# SCH_Potensiometers_2024-04-15.net
KiCad netlist of a schematic drawn in EasyEDA
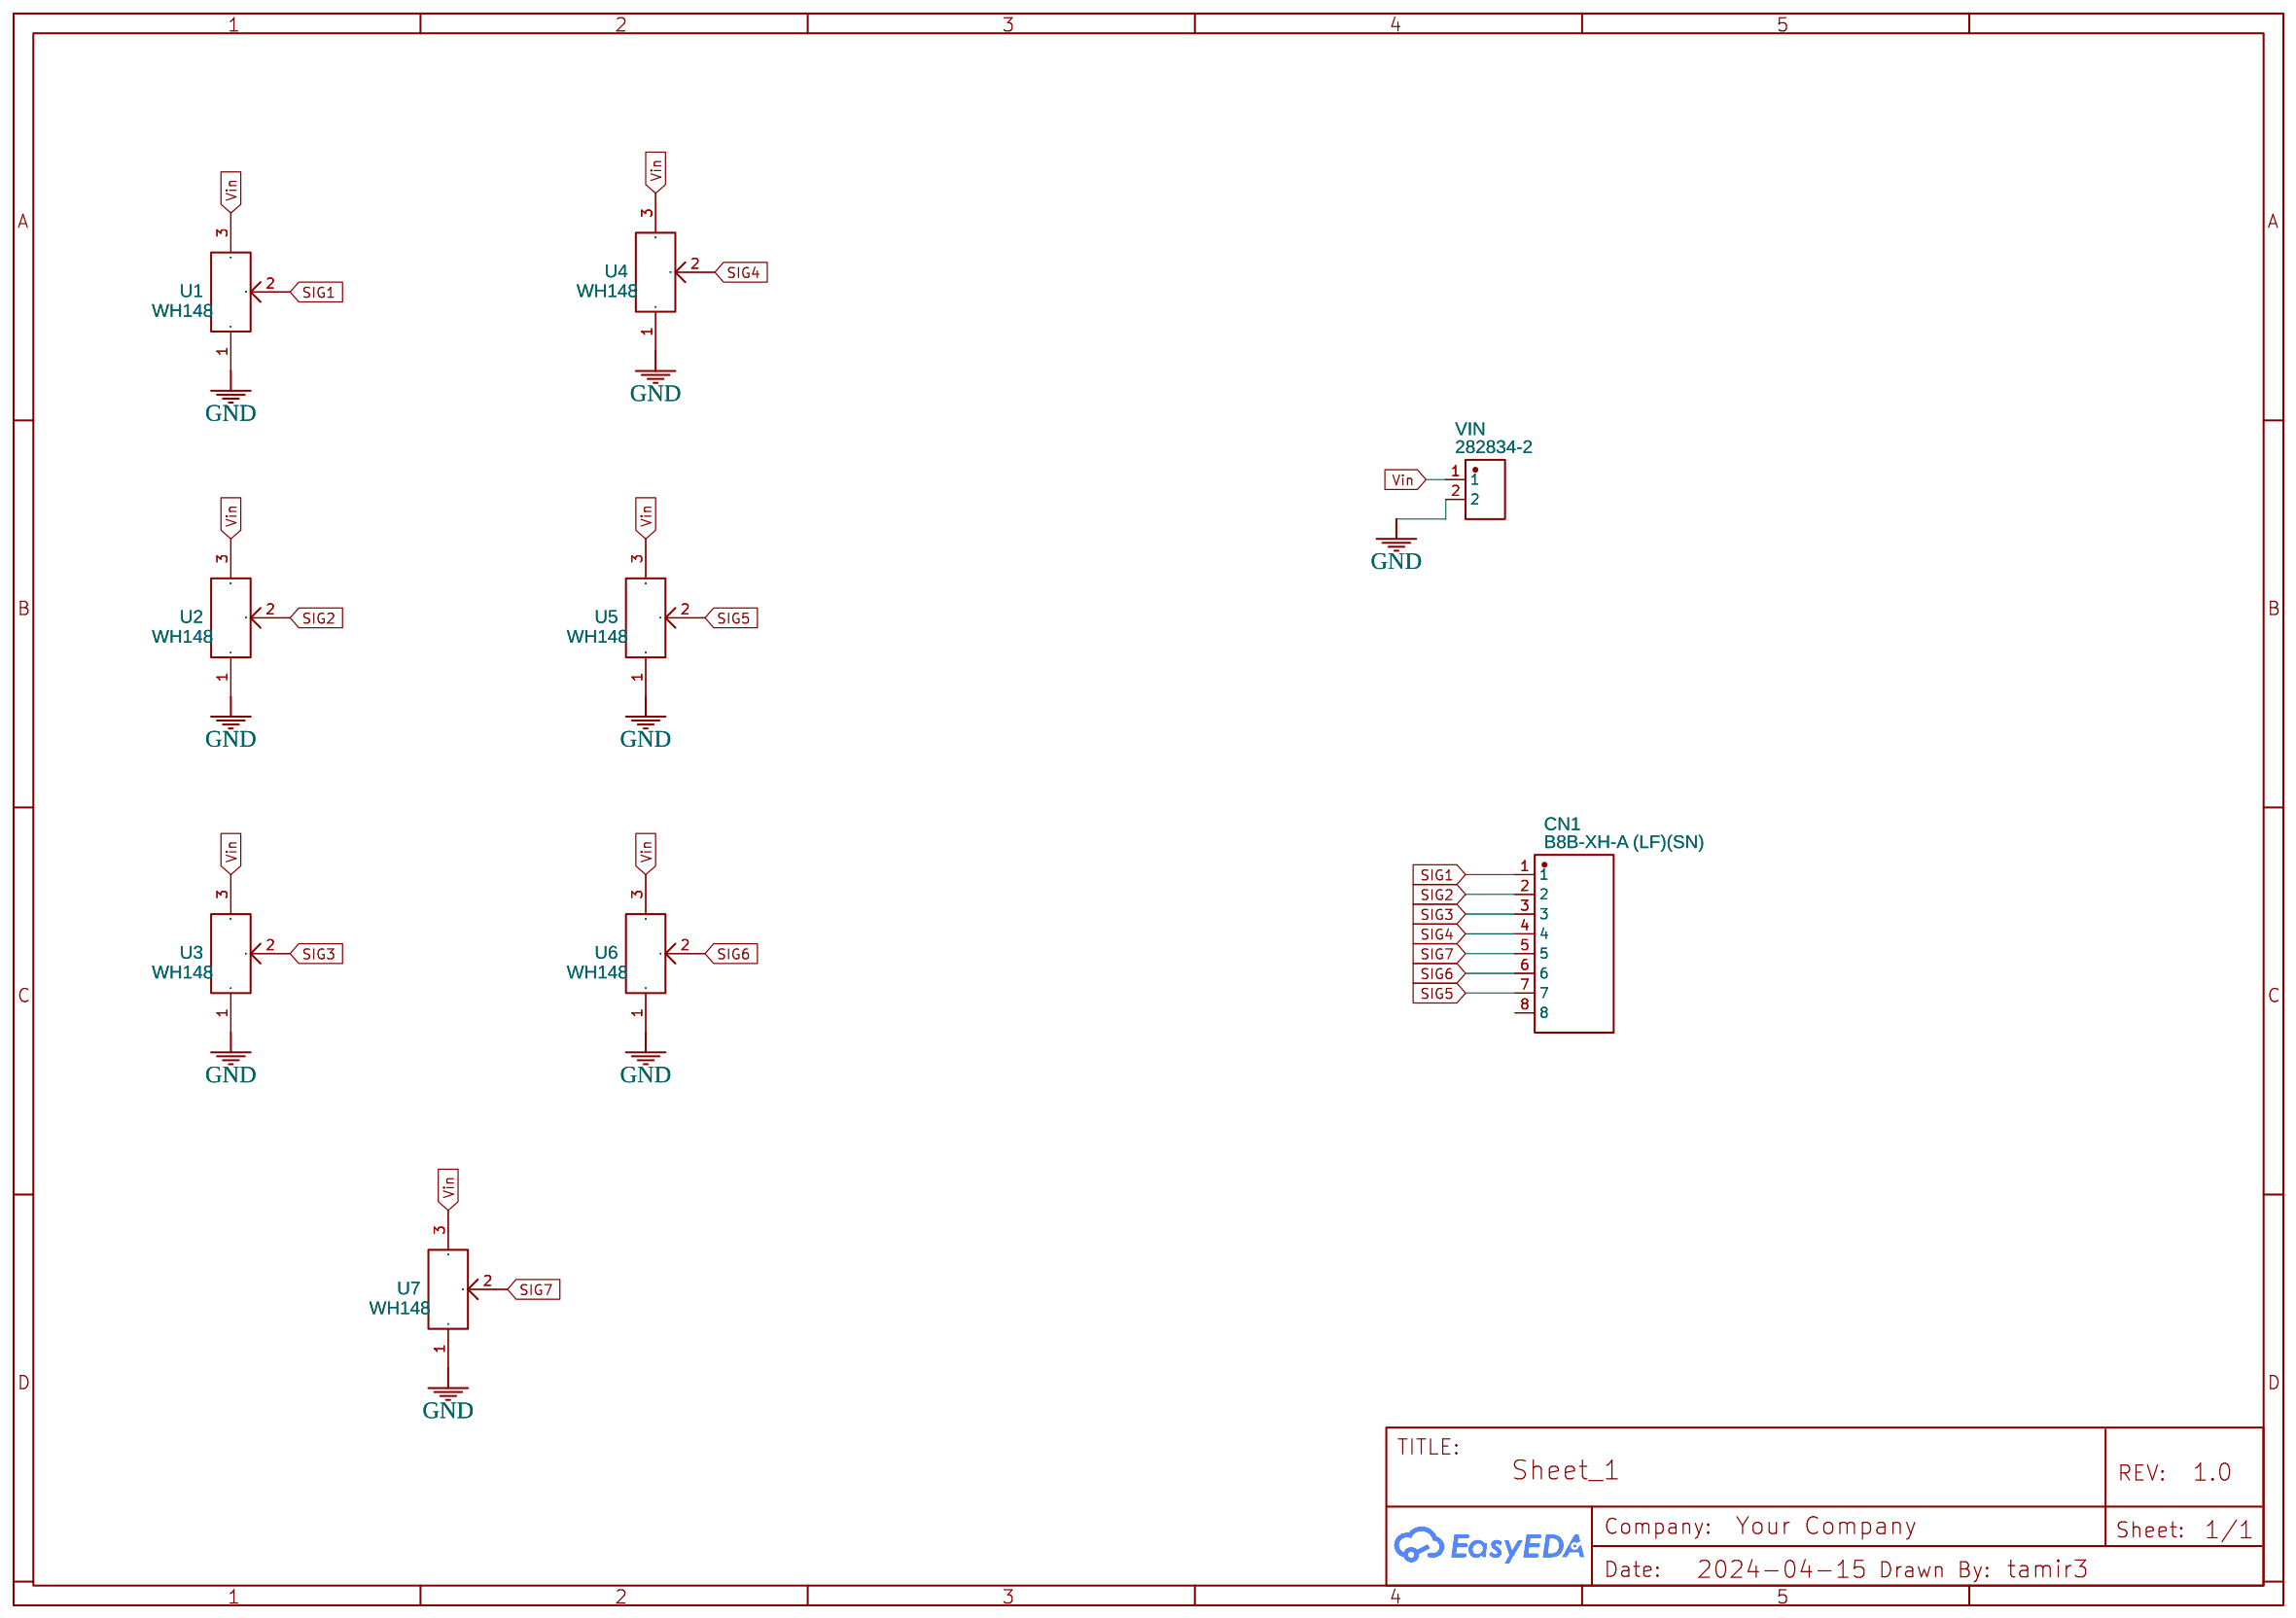
[diagram p0: schematic sheet]

(export (version "E")
  (design (tool "Eeschema 10.0.6"))
  (components
    (comp (ref "CN1")
      (value "B8B-XH-A (LF)(SN)")
      (fields (field (name "Manufacturer Part") "B8B-XH-A(LF)(SN)") (field (name "Manufacturer") "JST"))
      (libsource (lib "") (part "B8B-XH-A (LF)(SN)"))
    )
    (comp (ref "U1") (value "WH148") (libsource (lib "") (part "WH148 POTENZIOMETRO A SALDARE ORIZZONTALE")))
    (comp (ref "U2") (value "WH148") (libsource (lib "") (part "WH148 POTENZIOMETRO A SALDARE ORIZZONTALE")))
    (comp (ref "U3") (value "WH148") (libsource (lib "") (part "WH148 POTENZIOMETRO A SALDARE ORIZZONTALE")))
    (comp (ref "U4") (value "WH148") (libsource (lib "") (part "WH148 POTENZIOMETRO A SALDARE ORIZZONTALE")))
    (comp (ref "U5") (value "WH148") (libsource (lib "") (part "WH148 POTENZIOMETRO A SALDARE ORIZZONTALE")))
    (comp (ref "U6") (value "WH148") (libsource (lib "") (part "WH148 POTENZIOMETRO A SALDARE ORIZZONTALE")))
    (comp (ref "U7") (value "WH148") (libsource (lib "") (part "WH148 POTENZIOMETRO A SALDARE ORIZZONTALE")))
    (comp (ref "VIN")
      (value "282834-2")
      (fields (field (name "Manufacturer") "TE Connectivity(泰科电子)"))
      (libsource (lib "") (part "282834-2"))
    )
  )
  (nets
    (net (code "1") (name "GND") (class "Default")
      (node (ref "U1") (pin "1") (pinfunction "T1_1") (pintype "unspecified"))
      (node (ref "U2") (pin "1") (pinfunction "T1_1") (pintype "unspecified"))
      (node (ref "U3") (pin "1") (pinfunction "T1_1") (pintype "unspecified"))
      (node (ref "U4") (pin "1") (pinfunction "T1_1") (pintype "unspecified"))
      (node (ref "U5") (pin "1") (pinfunction "T1_1") (pintype "unspecified"))
      (node (ref "U6") (pin "1") (pinfunction "T1_1") (pintype "unspecified"))
      (node (ref "U7") (pin "1") (pinfunction "T1_1") (pintype "unspecified"))
      (node (ref "VIN") (pin "2") (pinfunction "2_2") (pintype "unspecified"))
    )
    (net (code "2") (name "SIG1") (class "Default")
      (node (ref "CN1") (pin "1") (pinfunction "1_1") (pintype "unspecified"))
      (node (ref "U1") (pin "2") (pinfunction "T2_2") (pintype "unspecified"))
    )
    (net (code "3") (name "SIG2") (class "Default")
      (node (ref "CN1") (pin "2") (pinfunction "2_2") (pintype "unspecified"))
      (node (ref "U2") (pin "2") (pinfunction "T2_2") (pintype "unspecified"))
    )
    (net (code "4") (name "SIG3") (class "Default")
      (node (ref "CN1") (pin "3") (pinfunction "3_3") (pintype "unspecified"))
      (node (ref "U3") (pin "2") (pinfunction "T2_2") (pintype "unspecified"))
    )
    (net (code "5") (name "SIG4") (class "Default")
      (node (ref "CN1") (pin "4") (pinfunction "4_4") (pintype "unspecified"))
      (node (ref "U4") (pin "2") (pinfunction "T2_2") (pintype "unspecified"))
    )
    (net (code "6") (name "SIG5") (class "Default")
      (node (ref "CN1") (pin "7") (pinfunction "7_7") (pintype "unspecified"))
      (node (ref "U5") (pin "2") (pinfunction "T2_2") (pintype "unspecified"))
    )
    (net (code "7") (name "SIG6") (class "Default")
      (node (ref "CN1") (pin "6") (pinfunction "6_6") (pintype "unspecified"))
      (node (ref "U6") (pin "2") (pinfunction "T2_2") (pintype "unspecified"))
    )
    (net (code "8") (name "SIG7") (class "Default")
      (node (ref "CN1") (pin "5") (pinfunction "5_5") (pintype "unspecified"))
      (node (ref "U7") (pin "2") (pinfunction "T2_2") (pintype "unspecified"))
    )
    (net (code "9") (name "Vin") (class "Default")
      (node (ref "U1") (pin "3") (pinfunction "T3_3") (pintype "unspecified"))
      (node (ref "U2") (pin "3") (pinfunction "T3_3") (pintype "unspecified"))
      (node (ref "U3") (pin "3") (pinfunction "T3_3") (pintype "unspecified"))
      (node (ref "U4") (pin "3") (pinfunction "T3_3") (pintype "unspecified"))
      (node (ref "U5") (pin "3") (pinfunction "T3_3") (pintype "unspecified"))
      (node (ref "U6") (pin "3") (pinfunction "T3_3") (pintype "unspecified"))
      (node (ref "U7") (pin "3") (pinfunction "T3_3") (pintype "unspecified"))
      (node (ref "VIN") (pin "1") (pinfunction "1_1") (pintype "unspecified"))
    )
    (net (code "10") (name "unconnected-(CN1-Pad8)") (class "Default")
      (node (ref "CN1") (pin "8") (pinfunction "8_8") (pintype "unspecified"))
    )
  )
)
